# Sheet2.net
KiCad netlist of a schematic drawn in Altium Designer
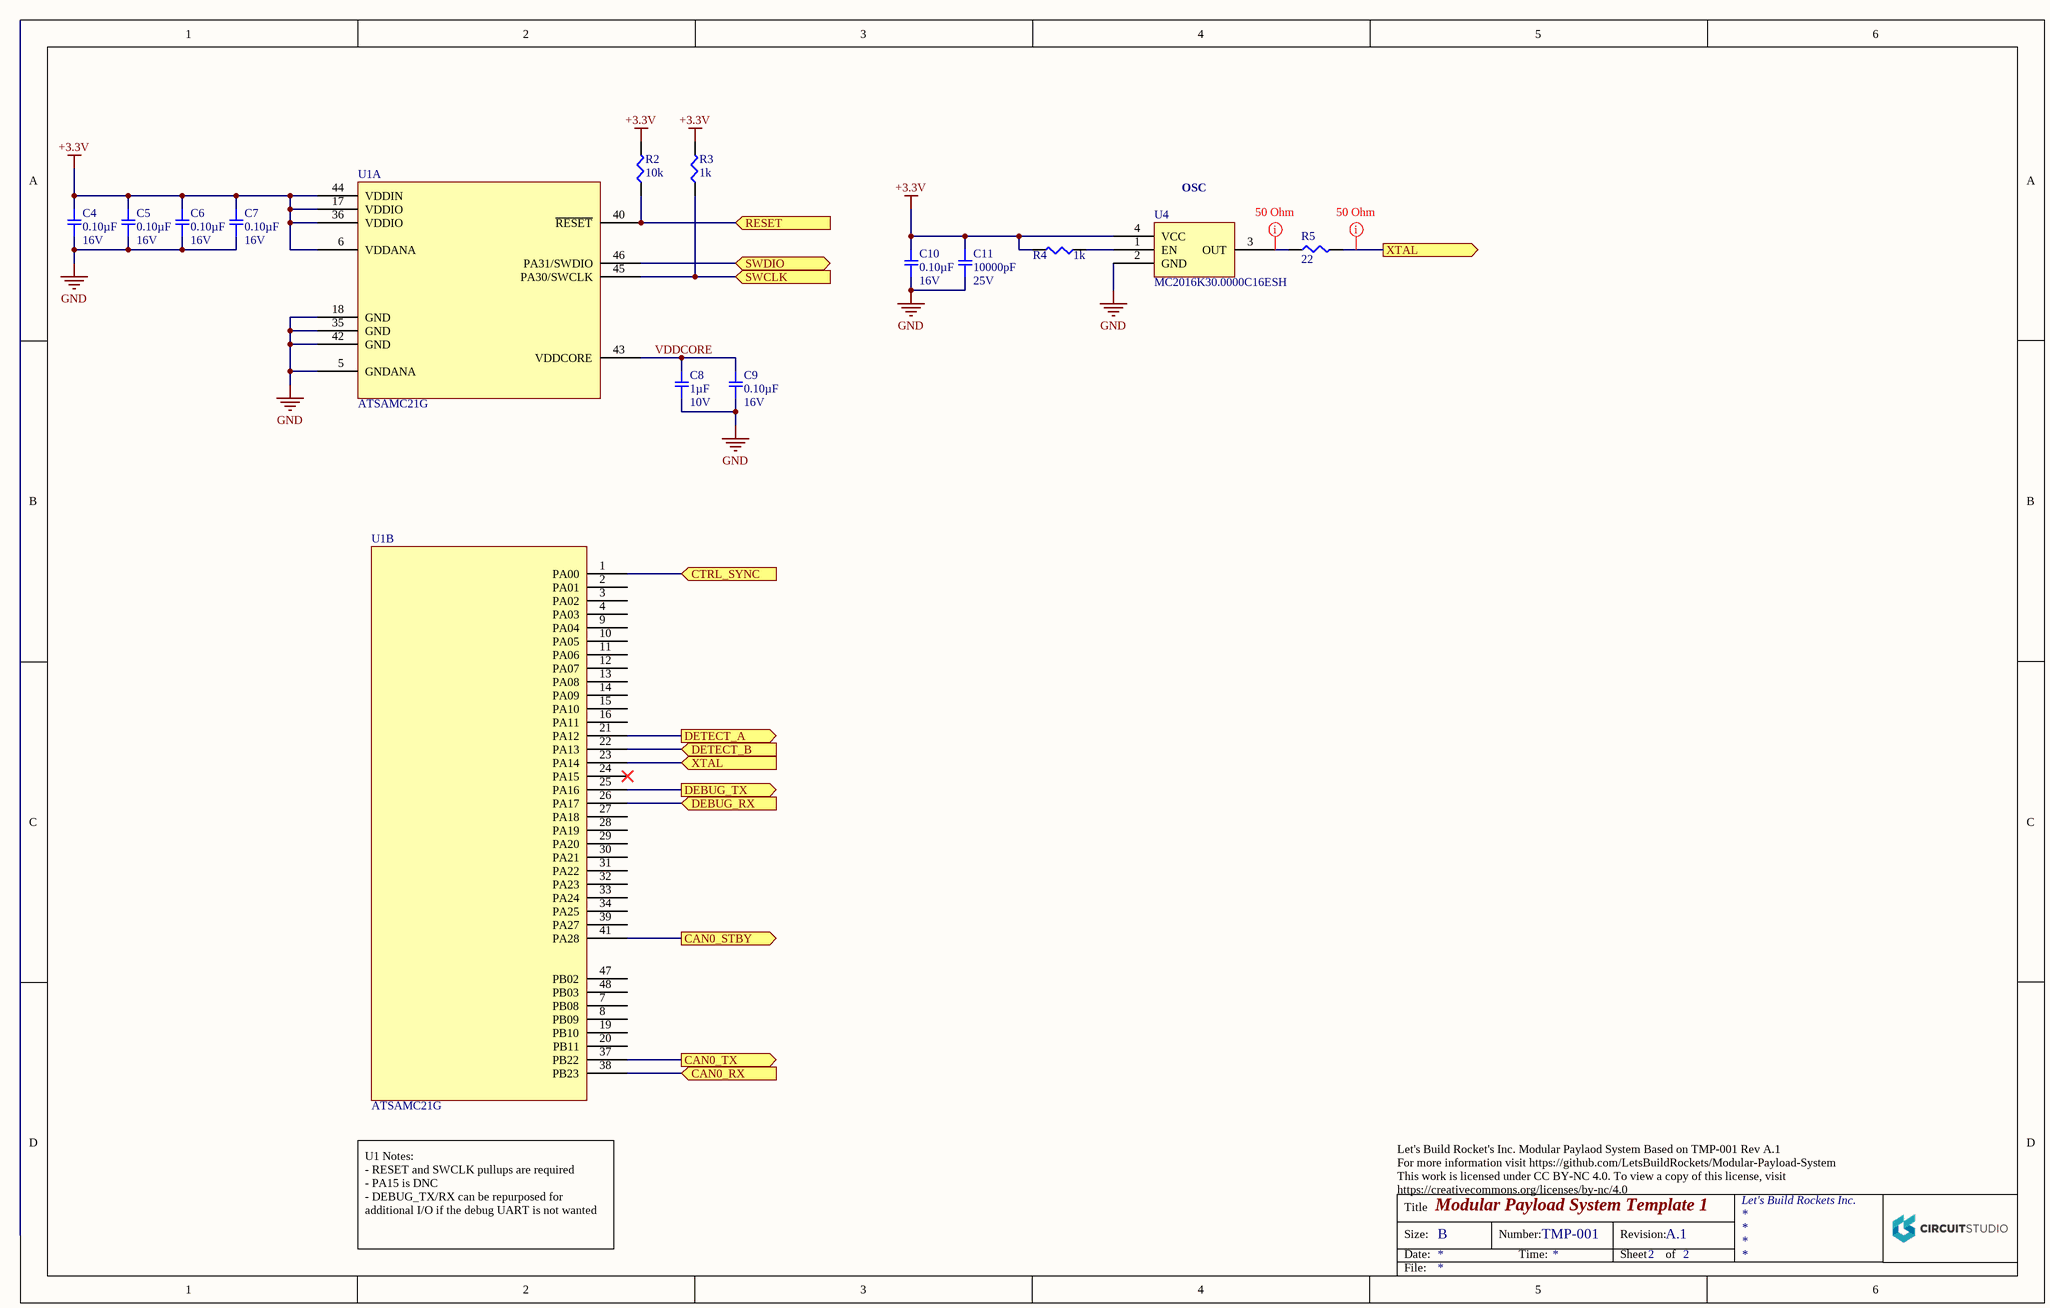
[diagram p0: Sheet2.SchDoc]

(export (version "E")
  (design (tool "Eeschema 10.0.6"))
  (components
    (comp (ref "C4")
      (value "0.10µF")
      (footprint "SMD-0402C")
      (description "CAP CER 0.1UF 16V X7R 0402")
      (fields
        (field (name "DIGI-KEY PART NUMBER") "490-4759-1-ND")
        (field (name "PART NUMBER") "GCM155R71C104KA55D")
        (field (name "VOLTAGE") "16V")
      )
      (libsource (lib "capacitor_murata_0402") (part "GCM155R71C104KA55D"))
    )
    (comp (ref "C5")
      (value "0.10µF")
      (footprint "SMD-0402C")
      (description "CAP CER 0.1UF 16V X7R 0402")
      (fields
        (field (name "DIGI-KEY PART NUMBER") "490-4759-1-ND")
        (field (name "PART NUMBER") "GCM155R71C104KA55D")
        (field (name "VOLTAGE") "16V")
      )
      (libsource (lib "capacitor_murata_0402") (part "GCM155R71C104KA55D"))
    )
    (comp (ref "C6")
      (value "0.10µF")
      (footprint "SMD-0402C")
      (description "CAP CER 0.1UF 16V X7R 0402")
      (fields
        (field (name "DIGI-KEY PART NUMBER") "490-4759-1-ND")
        (field (name "PART NUMBER") "GCM155R71C104KA55D")
        (field (name "VOLTAGE") "16V")
      )
      (libsource (lib "capacitor_murata_0402") (part "GCM155R71C104KA55D"))
    )
    (comp (ref "C7")
      (value "0.10µF")
      (footprint "SMD-0402C")
      (description "CAP CER 0.1UF 16V X7R 0402")
      (fields
        (field (name "DIGI-KEY PART NUMBER") "490-4759-1-ND")
        (field (name "PART NUMBER") "GCM155R71C104KA55D")
        (field (name "VOLTAGE") "16V")
      )
      (libsource (lib "capacitor_murata_0402") (part "GCM155R71C104KA55D"))
    )
    (comp (ref "C8")
      (value "1µF")
      (footprint "SMD-0402C")
      (description "CAP CER 1UF 10V X7S 0402")
      (fields
        (field (name "DIGI-KEY PART NUMBER") "490-13409-1-ND")
        (field (name "PART NUMBER") "GCM155C71A105KE38D")
        (field (name "VOLTAGE") "10V")
      )
      (libsource (lib "capacitor_murata_0402") (part "GCM155C71A105KE38D"))
    )
    (comp (ref "C9")
      (value "0.10µF")
      (footprint "SMD-0402C")
      (description "CAP CER 0.1UF 16V X7R 0402")
      (fields
        (field (name "DIGI-KEY PART NUMBER") "490-4759-1-ND")
        (field (name "PART NUMBER") "GCM155R71C104KA55D")
        (field (name "VOLTAGE") "16V")
      )
      (libsource (lib "capacitor_murata_0402") (part "GCM155R71C104KA55D"))
    )
    (comp (ref "C10")
      (value "0.10µF")
      (footprint "SMD-0402C")
      (description "CAP CER 0.1UF 16V X7R 0402")
      (fields
        (field (name "DIGI-KEY PART NUMBER") "490-4759-1-ND")
        (field (name "PART NUMBER") "GCM155R71C104KA55D")
        (field (name "VOLTAGE") "16V")
      )
      (libsource (lib "capacitor_murata_0402") (part "GCM155R71C104KA55D"))
    )
    (comp (ref "C11")
      (value "10000pF")
      (footprint "SMD-0402C")
      (description "CAP CER 10000PF 25V X7R 0402")
      (fields
        (field (name "DIGI-KEY PART NUMBER") "490-6043-1-ND")
        (field (name "PART NUMBER") "GCM155R71E103KA37D")
        (field (name "VOLTAGE") "25V")
      )
      (libsource (lib "capacitor_murata_0402") (part "GCM155R71E103KA37D"))
    )
    (comp (ref "R2")
      (value "10k")
      (footprint "SMD-0402-RES")
      (description "RES SMD 10K OHM 5% 1/10W 0402")
      (fields (field (name "PART NUMBER") "ERJ-2GEJ103X") (field (name "DIGI-KEY PART NUMBER") "P10KJCT-ND"))
      (libsource (lib "Panasonic_ERJ_0402") (part "ERJ-2GEJ103X"))
    )
    (comp (ref "R3")
      (value "1k")
      (footprint "SMD-0402-RES")
      (description "RES SMD 1K OHM 5% 1/10W 0402")
      (fields (field (name "PART NUMBER") "ERJ-2GEJ102X") (field (name "DIGI-KEY PART NUMBER") "P1.0KJCT-ND"))
      (libsource (lib "Panasonic_ERJ_0402") (part "ERJ-2GEJ102X"))
    )
    (comp (ref "R4")
      (value "1k")
      (footprint "SMD-0402-RES")
      (description "RES SMD 1K OHM 5% 1/10W 0402")
      (fields (field (name "PART NUMBER") "ERJ-2GEJ102X") (field (name "DIGI-KEY PART NUMBER") "P1.0KJCT-ND"))
      (libsource (lib "Panasonic_ERJ_0402") (part "ERJ-2GEJ102X"))
    )
    (comp (ref "R5")
      (value "22")
      (footprint "SMD-0402-RES")
      (description "RES SMD 22 OHM 1% 1/10W 0402")
      (fields
        (field (name "PART NUMBER") "ERJ-2RKF22R0X")
        (field (name "DIGI-KEY PART NUMBER") "P22.0LCT-ND")
      )
      (libsource (lib "Panasonic_ERJ_0402") (part "ERJ-2RKF22R0X"))
    )
    (comp (ref "U1")
      (value "ATSAMC21G")
      (footprint "TSQFP50P900X900X120-48N")
      (libsource (lib "ModularPayload") (part "ATSAMC21G"))
    )
    (comp (ref "U4")
      (value "MC2016K30.0000C16ESH")
      (footprint "MC2016")
      (libsource (lib "ModularPayload") (part "MC2016K30.0000C16ESH"))
    )
  )
  (nets
    (net (code "1") (name "+3.3V") (class "Default")
      (node (ref "C10") (pin "2") (pinfunction "2_2") (pintype "passive"))
      (node (ref "C11") (pin "2") (pinfunction "2_2") (pintype "passive"))
      (node (ref "C4") (pin "2") (pinfunction "2_2") (pintype "passive"))
      (node (ref "C5") (pin "2") (pinfunction "2_2") (pintype "passive"))
      (node (ref "C6") (pin "2") (pinfunction "2_2") (pintype "passive"))
      (node (ref "C7") (pin "2") (pinfunction "2_2") (pintype "passive"))
      (node (ref "R2") (pin "2") (pinfunction "2_2") (pintype "passive"))
      (node (ref "R3") (pin "2") (pinfunction "2_2") (pintype "passive"))
      (node (ref "R4") (pin "2") (pinfunction "2_2") (pintype "passive"))
      (node (ref "U1") (pin "17") (pinfunction "VDDIO_17") (pintype "passive"))
      (node (ref "U1") (pin "36") (pinfunction "VDDIO_36") (pintype "passive"))
      (node (ref "U1") (pin "44") (pinfunction "VDDIN_44") (pintype "passive"))
      (node (ref "U1") (pin "6") (pinfunction "VDDANA_6") (pintype "passive"))
      (node (ref "U4") (pin "4") (pinfunction "VCC_4") (pintype "passive"))
    )
    (net (code "2") (name "/CAN0_RX") (class "Default")
      (node (ref "U1") (pin "38") (pinfunction "PB23_38") (pintype "passive"))
    )
    (net (code "3") (name "/CAN0_STBY") (class "Default")
      (node (ref "U1") (pin "41") (pinfunction "PA28_41") (pintype "passive"))
    )
    (net (code "4") (name "/CAN0_TX") (class "Default")
      (node (ref "U1") (pin "37") (pinfunction "PB22_37") (pintype "passive"))
    )
    (net (code "5") (name "/CTRL_SYNC") (class "Default")
      (node (ref "U1") (pin "1") (pinfunction "PA00_1") (pintype "passive"))
    )
    (net (code "6") (name "/DEBUG_RX") (class "Default")
      (node (ref "U1") (pin "26") (pinfunction "PA17_26") (pintype "passive"))
    )
    (net (code "7") (name "/DEBUG_TX") (class "Default")
      (node (ref "U1") (pin "25") (pinfunction "PA16_25") (pintype "passive"))
    )
    (net (code "8") (name "/DETECT_A") (class "Default")
      (node (ref "U1") (pin "21") (pinfunction "PA12_21") (pintype "passive"))
    )
    (net (code "9") (name "/DETECT_B") (class "Default")
      (node (ref "U1") (pin "22") (pinfunction "PA13_22") (pintype "passive"))
    )
    (net (code "10") (name "/RESET") (class "Default")
      (node (ref "R2") (pin "1") (pinfunction "1_1") (pintype "passive"))
      (node (ref "U1") (pin "40") (pinfunction "~{RESET}_40") (pintype "passive"))
    )
    (net (code "11") (name "/SWCLK") (class "Default")
      (node (ref "R3") (pin "1") (pinfunction "1_1") (pintype "passive"))
      (node (ref "U1") (pin "45") (pinfunction "PA30/SWCLK_45") (pintype "passive"))
    )
    (net (code "12") (name "/SWDIO") (class "Default")
      (node (ref "U1") (pin "46") (pinfunction "PA31/SWDIO_46") (pintype "passive"))
    )
    (net (code "13") (name "/VDDCORE") (class "Default")
      (node (ref "C8") (pin "2") (pinfunction "2_2") (pintype "passive"))
      (node (ref "C9") (pin "2") (pinfunction "2_2") (pintype "passive"))
      (node (ref "U1") (pin "43") (pinfunction "VDDCORE_43") (pintype "passive"))
    )
    (net (code "14") (name "/XTAL") (class "Default")
      (node (ref "R5") (pin "2") (pinfunction "2_2") (pintype "passive"))
      (node (ref "U1") (pin "23") (pinfunction "PA14_23") (pintype "passive"))
    )
    (net (code "15") (name "GND") (class "Default")
      (node (ref "C10") (pin "1") (pinfunction "1_1") (pintype "passive"))
      (node (ref "C11") (pin "1") (pinfunction "1_1") (pintype "passive"))
      (node (ref "C4") (pin "1") (pinfunction "1_1") (pintype "passive"))
      (node (ref "C5") (pin "1") (pinfunction "1_1") (pintype "passive"))
      (node (ref "C6") (pin "1") (pinfunction "1_1") (pintype "passive"))
      (node (ref "C7") (pin "1") (pinfunction "1_1") (pintype "passive"))
      (node (ref "C8") (pin "1") (pinfunction "1_1") (pintype "passive"))
      (node (ref "C9") (pin "1") (pinfunction "1_1") (pintype "passive"))
      (node (ref "U1") (pin "18") (pinfunction "GND_18") (pintype "passive"))
      (node (ref "U1") (pin "35") (pinfunction "GND_35") (pintype "passive"))
      (node (ref "U1") (pin "42") (pinfunction "GND_42") (pintype "passive"))
      (node (ref "U1") (pin "5") (pinfunction "GNDANA_5") (pintype "passive"))
      (node (ref "U4") (pin "2") (pinfunction "GND_2") (pintype "passive"))
    )
    (net (code "16") (name "Net-(U4-EN)") (class "Default")
      (node (ref "R4") (pin "1") (pinfunction "1_1") (pintype "passive"))
      (node (ref "U4") (pin "1") (pinfunction "EN_1") (pintype "passive"))
    )
    (net (code "17") (name "Net-(U4-OUT)") (class "Default")
      (node (ref "R5") (pin "1") (pinfunction "1_1") (pintype "passive"))
      (node (ref "U4") (pin "3") (pinfunction "OUT_3") (pintype "passive"))
    )
    (net (code "18") (name "unconnected-(U1B-PA01-Pad2)") (class "Default")
      (node (ref "U1") (pin "2") (pinfunction "PA01_2") (pintype "passive"))
    )
    (net (code "19") (name "unconnected-(U1B-PA02-Pad3)") (class "Default")
      (node (ref "U1") (pin "3") (pinfunction "PA02_3") (pintype "passive"))
    )
    (net (code "20") (name "unconnected-(U1B-PA03-Pad4)") (class "Default")
      (node (ref "U1") (pin "4") (pinfunction "PA03_4") (pintype "passive"))
    )
    (net (code "21") (name "unconnected-(U1B-PA04-Pad9)") (class "Default")
      (node (ref "U1") (pin "9") (pinfunction "PA04_9") (pintype "passive"))
    )
    (net (code "22") (name "unconnected-(U1B-PA05-Pad10)") (class "Default")
      (node (ref "U1") (pin "10") (pinfunction "PA05_10") (pintype "passive"))
    )
    (net (code "23") (name "unconnected-(U1B-PA06-Pad11)") (class "Default")
      (node (ref "U1") (pin "11") (pinfunction "PA06_11") (pintype "passive"))
    )
    (net (code "24") (name "unconnected-(U1B-PA07-Pad12)") (class "Default")
      (node (ref "U1") (pin "12") (pinfunction "PA07_12") (pintype "passive"))
    )
    (net (code "25") (name "unconnected-(U1B-PA08-Pad13)") (class "Default")
      (node (ref "U1") (pin "13") (pinfunction "PA08_13") (pintype "passive"))
    )
    (net (code "26") (name "unconnected-(U1B-PA09-Pad14)") (class "Default")
      (node (ref "U1") (pin "14") (pinfunction "PA09_14") (pintype "passive"))
    )
    (net (code "27") (name "unconnected-(U1B-PA10-Pad15)") (class "Default")
      (node (ref "U1") (pin "15") (pinfunction "PA10_15") (pintype "passive"))
    )
    (net (code "28") (name "unconnected-(U1B-PA11-Pad16)") (class "Default")
      (node (ref "U1") (pin "16") (pinfunction "PA11_16") (pintype "passive"))
    )
    (net (code "29") (name "unconnected-(U1B-PA15-Pad24)") (class "Default")
      (node (ref "U1") (pin "24") (pinfunction "PA15_24") (pintype "passive+no_connect"))
    )
    (net (code "30") (name "unconnected-(U1B-PA18-Pad27)") (class "Default")
      (node (ref "U1") (pin "27") (pinfunction "PA18_27") (pintype "passive"))
    )
    (net (code "31") (name "unconnected-(U1B-PA19-Pad28)") (class "Default")
      (node (ref "U1") (pin "28") (pinfunction "PA19_28") (pintype "passive"))
    )
    (net (code "32") (name "unconnected-(U1B-PA20-Pad29)") (class "Default")
      (node (ref "U1") (pin "29") (pinfunction "PA20_29") (pintype "passive"))
    )
    (net (code "33") (name "unconnected-(U1B-PA21-Pad30)") (class "Default")
      (node (ref "U1") (pin "30") (pinfunction "PA21_30") (pintype "passive"))
    )
    (net (code "34") (name "unconnected-(U1B-PA22-Pad31)") (class "Default")
      (node (ref "U1") (pin "31") (pinfunction "PA22_31") (pintype "passive"))
    )
    (net (code "35") (name "unconnected-(U1B-PA23-Pad32)") (class "Default")
      (node (ref "U1") (pin "32") (pinfunction "PA23_32") (pintype "passive"))
    )
    (net (code "36") (name "unconnected-(U1B-PA24-Pad33)") (class "Default")
      (node (ref "U1") (pin "33") (pinfunction "PA24_33") (pintype "passive"))
    )
    (net (code "37") (name "unconnected-(U1B-PA25-Pad34)") (class "Default")
      (node (ref "U1") (pin "34") (pinfunction "PA25_34") (pintype "passive"))
    )
    (net (code "38") (name "unconnected-(U1B-PA27-Pad39)") (class "Default")
      (node (ref "U1") (pin "39") (pinfunction "PA27_39") (pintype "passive"))
    )
    (net (code "39") (name "unconnected-(U1B-PB02-Pad47)") (class "Default")
      (node (ref "U1") (pin "47") (pinfunction "PB02_47") (pintype "passive"))
    )
    (net (code "40") (name "unconnected-(U1B-PB03-Pad48)") (class "Default")
      (node (ref "U1") (pin "48") (pinfunction "PB03_48") (pintype "passive"))
    )
    (net (code "41") (name "unconnected-(U1B-PB08-Pad7)") (class "Default")
      (node (ref "U1") (pin "7") (pinfunction "PB08_7") (pintype "passive"))
    )
    (net (code "42") (name "unconnected-(U1B-PB09-Pad8)") (class "Default")
      (node (ref "U1") (pin "8") (pinfunction "PB09_8") (pintype "passive"))
    )
    (net (code "43") (name "unconnected-(U1B-PB10-Pad19)") (class "Default")
      (node (ref "U1") (pin "19") (pinfunction "PB10_19") (pintype "passive"))
    )
    (net (code "44") (name "unconnected-(U1B-PB11-Pad20)") (class "Default")
      (node (ref "U1") (pin "20") (pinfunction "PB11_20") (pintype "passive"))
    )
  )
)
